# IR.net
KiCad netlist of a schematic drawn in Altium Designer
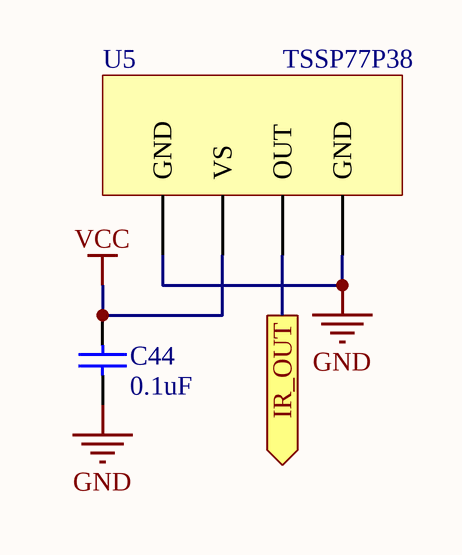
[diagram p0: IR.SchDoc]

(export (version "E")
  (design (tool "Eeschema 10.0.6"))
  (components
    (comp (ref "C44")
      (value "0.1uF")
      (footprint "C0402[1005X55]")
      (description "0.1uF 6.3V 10% 0402 (1005 Metric)")
      (fields (field (name "PARTNUMBER") "GRM155R70J104KA01D") (field (name "MANUFACTURER") "Murata"))
      (libsource (lib "Capacitors") (part "CAP_0.1uF_6.3V_0402_10%"))
    )
    (comp (ref "U5")
      (value "TSSP77P38")
      (footprint "TSSP77P38")
      (fields (field (name "MANUFACTURER") "Vishay"))
      (libsource (lib "Components") (part "TSSP77P38"))
    )
  )
  (nets
    (net (code "1") (name "/IR_OUT") (class "Default")
      (node (ref "U5") (pin "3") (pinfunction "OUT_3") (pintype "passive"))
    )
    (net (code "2") (name "GND") (class "Default")
      (node (ref "C44") (pin "1") (pinfunction "1_1") (pintype "passive"))
      (node (ref "U5") (pin "1") (pinfunction "GND_1") (pintype "passive"))
      (node (ref "U5") (pin "4") (pinfunction "GND_4") (pintype "passive"))
    )
    (net (code "3") (name "VCC") (class "Default")
      (node (ref "C44") (pin "2") (pinfunction "2_2") (pintype "passive"))
      (node (ref "U5") (pin "2") (pinfunction "VS_2") (pintype "passive"))
    )
  )
)
